# SCH_Slackpad.net
KiCad netlist of a schematic drawn in EasyEDA
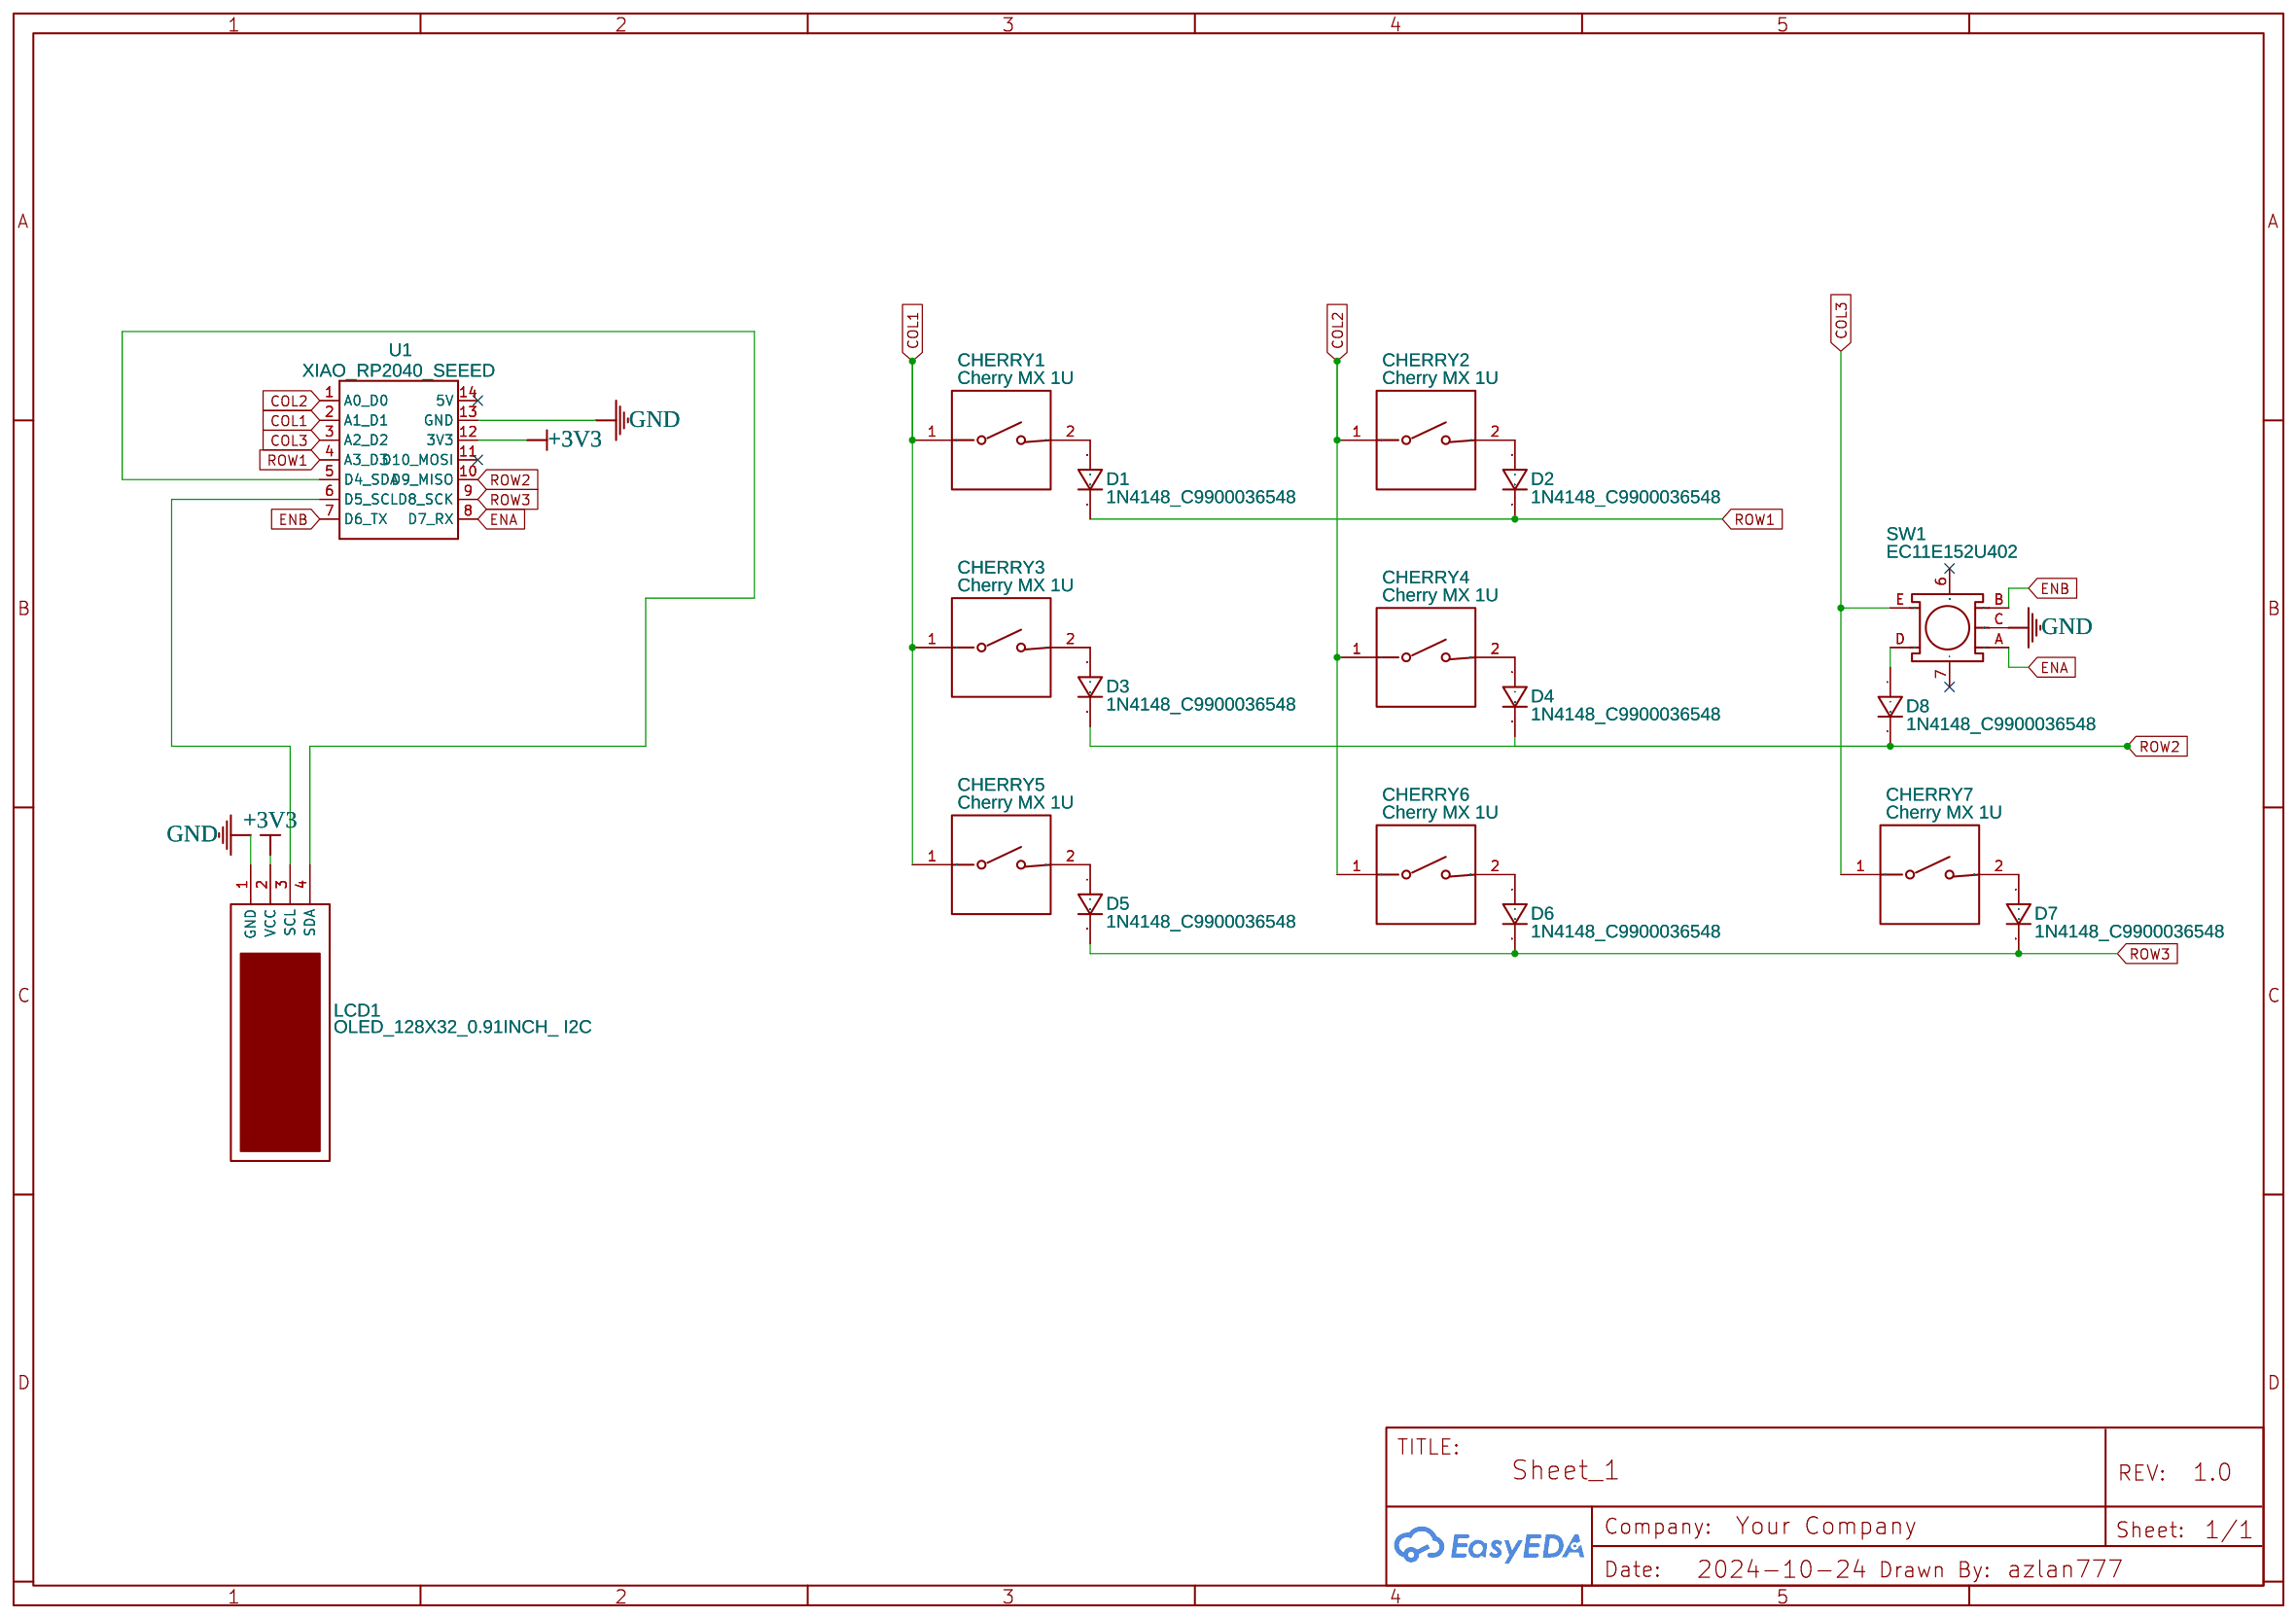
[diagram p0: schematic sheet]

(export (version "E")
  (design (tool "Eeschema 10.0.6"))
  (components
    (comp (ref "CHERRY1") (value "Cherry MX 1U") (libsource (lib "") (part "Cherry MX 1U")))
    (comp (ref "CHERRY2") (value "Cherry MX 1U") (libsource (lib "") (part "Cherry MX 1U")))
    (comp (ref "CHERRY3") (value "Cherry MX 1U") (libsource (lib "") (part "Cherry MX 1U")))
    (comp (ref "CHERRY4") (value "Cherry MX 1U") (libsource (lib "") (part "Cherry MX 1U")))
    (comp (ref "CHERRY5") (value "Cherry MX 1U") (libsource (lib "") (part "Cherry MX 1U")))
    (comp (ref "CHERRY6") (value "Cherry MX 1U") (libsource (lib "") (part "Cherry MX 1U")))
    (comp (ref "CHERRY7") (value "Cherry MX 1U") (libsource (lib "") (part "Cherry MX 1U")))
    (comp (ref "D1")
      (value "1N4148_C9900036548")
      (fields (field (name "Manufacturer Part") "1N4148"))
      (libsource (lib "") (part "1N4148_C9900036548"))
    )
    (comp (ref "D2")
      (value "1N4148_C9900036548")
      (fields (field (name "Manufacturer Part") "1N4148"))
      (libsource (lib "") (part "1N4148_C9900036548"))
    )
    (comp (ref "D3")
      (value "1N4148_C9900036548")
      (fields (field (name "Manufacturer Part") "1N4148"))
      (libsource (lib "") (part "1N4148_C9900036548"))
    )
    (comp (ref "D4")
      (value "1N4148_C9900036548")
      (fields (field (name "Manufacturer Part") "1N4148"))
      (libsource (lib "") (part "1N4148_C9900036548"))
    )
    (comp (ref "D5")
      (value "1N4148_C9900036548")
      (fields (field (name "Manufacturer Part") "1N4148"))
      (libsource (lib "") (part "1N4148_C9900036548"))
    )
    (comp (ref "D6")
      (value "1N4148_C9900036548")
      (fields (field (name "Manufacturer Part") "1N4148"))
      (libsource (lib "") (part "1N4148_C9900036548"))
    )
    (comp (ref "D7")
      (value "1N4148_C9900036548")
      (fields (field (name "Manufacturer Part") "1N4148"))
      (libsource (lib "") (part "1N4148_C9900036548"))
    )
    (comp (ref "D8")
      (value "1N4148_C9900036548")
      (fields (field (name "Manufacturer Part") "1N4148"))
      (libsource (lib "") (part "1N4148_C9900036548"))
    )
    (comp (ref "LCD1")
      (value "OLED_128X32_0.91INCH_ I2C")
      (libsource (lib "") (part "OLED_128X32_0.91INCH_ I2C"))
    )
    (comp (ref "SW1")
      (value "EC11E152U402")
      (fields (field (name "Manufacturer") "ALPSALPINE(阿尔卑斯阿尔派)"))
      (libsource (lib "") (part "EC11E152U402"))
    )
    (comp (ref "U1") (value "XIAO_RP2040_SEEED") (libsource (lib "") (part "XIAO_RP2040_SEEED")))
  )
  (nets
    (net (code "1") (name "+3V3") (class "Default")
      (node (ref "LCD1") (pin "2") (pinfunction "VCC_2") (pintype "passive"))
      (node (ref "U1") (pin "12") (pinfunction "3V3_12") (pintype "bidirectional"))
    )
    (net (code "2") (name "COL1") (class "Default")
      (node (ref "CHERRY1") (pin "1") (pinfunction "1_1") (pintype "unspecified"))
      (node (ref "CHERRY3") (pin "1") (pinfunction "1_1") (pintype "unspecified"))
      (node (ref "CHERRY5") (pin "1") (pinfunction "1_1") (pintype "unspecified"))
      (node (ref "U1") (pin "2") (pinfunction "A1_D1_2") (pintype "bidirectional"))
    )
    (net (code "3") (name "COL2") (class "Default")
      (node (ref "CHERRY2") (pin "1") (pinfunction "1_1") (pintype "unspecified"))
      (node (ref "CHERRY4") (pin "1") (pinfunction "1_1") (pintype "unspecified"))
      (node (ref "CHERRY6") (pin "1") (pinfunction "1_1") (pintype "unspecified"))
      (node (ref "U1") (pin "1") (pinfunction "A0_D0_1") (pintype "bidirectional"))
    )
    (net (code "4") (name "COL3") (class "Default")
      (node (ref "CHERRY7") (pin "1") (pinfunction "1_1") (pintype "unspecified"))
      (node (ref "SW1") (pin "E") (pinfunction "E_E") (pintype "unspecified"))
      (node (ref "U1") (pin "3") (pinfunction "A2_D2_3") (pintype "bidirectional"))
    )
    (net (code "5") (name "ENA") (class "Default")
      (node (ref "SW1") (pin "A") (pinfunction "A_A") (pintype "unspecified"))
      (node (ref "U1") (pin "8") (pinfunction "D7_RX_8") (pintype "bidirectional"))
    )
    (net (code "6") (name "ENB") (class "Default")
      (node (ref "SW1") (pin "B") (pinfunction "B_B") (pintype "unspecified"))
      (node (ref "U1") (pin "7") (pinfunction "D6_TX_7") (pintype "bidirectional"))
    )
    (net (code "7") (name "GND") (class "Default")
      (node (ref "LCD1") (pin "1") (pinfunction "GND_1") (pintype "passive"))
      (node (ref "SW1") (pin "C") (pinfunction "C_C") (pintype "unspecified"))
      (node (ref "U1") (pin "13") (pinfunction "GND_13") (pintype "bidirectional"))
    )
    (net (code "8") (name "Net-(D1-A)") (class "Default")
      (node (ref "CHERRY1") (pin "2") (pinfunction "2_2") (pintype "unspecified"))
      (node (ref "D1") (pin "1") (pinfunction "A_1") (pintype "unspecified"))
    )
    (net (code "9") (name "Net-(D2-A)") (class "Default")
      (node (ref "CHERRY2") (pin "2") (pinfunction "2_2") (pintype "unspecified"))
      (node (ref "D2") (pin "1") (pinfunction "A_1") (pintype "unspecified"))
    )
    (net (code "10") (name "Net-(D3-A)") (class "Default")
      (node (ref "CHERRY3") (pin "2") (pinfunction "2_2") (pintype "unspecified"))
      (node (ref "D3") (pin "1") (pinfunction "A_1") (pintype "unspecified"))
    )
    (net (code "11") (name "Net-(D4-A)") (class "Default")
      (node (ref "CHERRY4") (pin "2") (pinfunction "2_2") (pintype "unspecified"))
      (node (ref "D4") (pin "1") (pinfunction "A_1") (pintype "unspecified"))
    )
    (net (code "12") (name "Net-(D5-A)") (class "Default")
      (node (ref "CHERRY5") (pin "2") (pinfunction "2_2") (pintype "unspecified"))
      (node (ref "D5") (pin "1") (pinfunction "A_1") (pintype "unspecified"))
    )
    (net (code "13") (name "Net-(D6-A)") (class "Default")
      (node (ref "CHERRY6") (pin "2") (pinfunction "2_2") (pintype "unspecified"))
      (node (ref "D6") (pin "1") (pinfunction "A_1") (pintype "unspecified"))
    )
    (net (code "14") (name "Net-(D7-A)") (class "Default")
      (node (ref "CHERRY7") (pin "2") (pinfunction "2_2") (pintype "unspecified"))
      (node (ref "D7") (pin "1") (pinfunction "A_1") (pintype "unspecified"))
    )
    (net (code "15") (name "Net-(D8-A)") (class "Default")
      (node (ref "D8") (pin "1") (pinfunction "A_1") (pintype "unspecified"))
      (node (ref "SW1") (pin "D") (pinfunction "D_D") (pintype "unspecified"))
    )
    (net (code "16") (name "Net-(LCD1-SCL)") (class "Default")
      (node (ref "LCD1") (pin "3") (pinfunction "SCL_3") (pintype "input"))
      (node (ref "U1") (pin "6") (pinfunction "D5_SCL_6") (pintype "bidirectional"))
    )
    (net (code "17") (name "Net-(LCD1-SDA)") (class "Default")
      (node (ref "LCD1") (pin "4") (pinfunction "SDA_4") (pintype "bidirectional"))
      (node (ref "U1") (pin "5") (pinfunction "D4_SDA_5") (pintype "bidirectional"))
    )
    (net (code "18") (name "ROW1") (class "Default")
      (node (ref "D1") (pin "2") (pinfunction "C_2") (pintype "unspecified"))
      (node (ref "D2") (pin "2") (pinfunction "C_2") (pintype "unspecified"))
      (node (ref "U1") (pin "4") (pinfunction "A3_D3_4") (pintype "bidirectional"))
    )
    (net (code "19") (name "ROW2") (class "Default")
      (node (ref "D3") (pin "2") (pinfunction "C_2") (pintype "unspecified"))
      (node (ref "D4") (pin "2") (pinfunction "C_2") (pintype "unspecified"))
      (node (ref "D8") (pin "2") (pinfunction "C_2") (pintype "unspecified"))
      (node (ref "U1") (pin "10") (pinfunction "D9_MISO_10") (pintype "bidirectional"))
    )
    (net (code "20") (name "ROW3") (class "Default")
      (node (ref "D5") (pin "2") (pinfunction "C_2") (pintype "unspecified"))
      (node (ref "D6") (pin "2") (pinfunction "C_2") (pintype "unspecified"))
      (node (ref "D7") (pin "2") (pinfunction "C_2") (pintype "unspecified"))
      (node (ref "U1") (pin "9") (pinfunction "D8_SCK_9") (pintype "bidirectional"))
    )
    (net (code "21") (name "unconnected-(SW1-Pad6)") (class "Default")
      (node (ref "SW1") (pin "6") (pinfunction "6_6") (pintype "unspecified+no_connect"))
    )
    (net (code "22") (name "unconnected-(SW1-Pad7)") (class "Default")
      (node (ref "SW1") (pin "7") (pinfunction "7_7") (pintype "unspecified+no_connect"))
    )
    (net (code "23") (name "unconnected-(U1-5V-Pad14)") (class "Default")
      (node (ref "U1") (pin "14") (pinfunction "5V_14") (pintype "bidirectional+no_connect"))
    )
    (net (code "24") (name "unconnected-(U1-D10_MOSI-Pad11)") (class "Default")
      (node (ref "U1") (pin "11") (pinfunction "D10_MOSI_11") (pintype "bidirectional+no_connect"))
    )
  )
)
